# MysensorsATSHA_EEprom.net
KiCad netlist of a schematic drawn in EAGLE
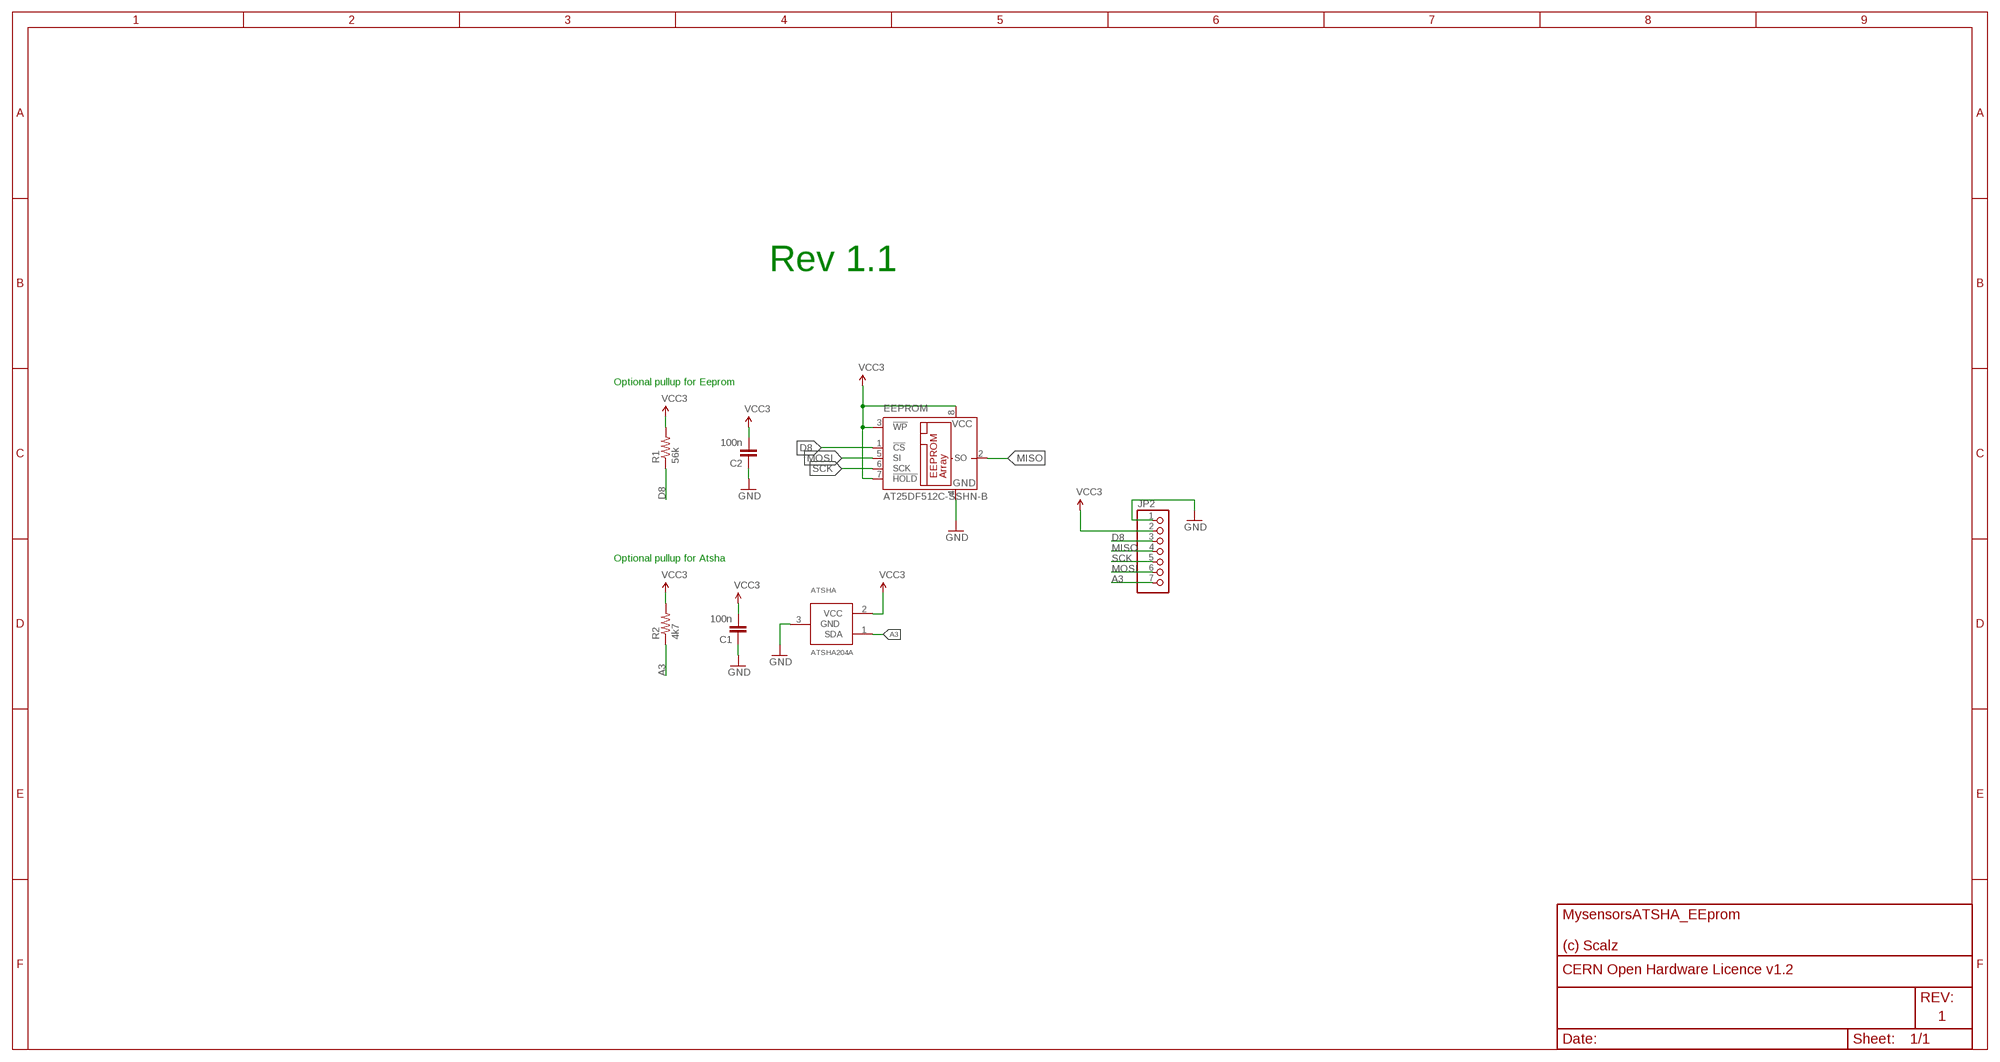
[diagram p0: schematic, sheet 1]

(export (version "E")
  (design (tool "Eeschema 10.0.6"))
  (components
    (comp (ref "ATSHA")
      (value "ATSHA204A")
      (footprint "eagle-import:SOT23")
      (libsource (lib "eagle-import") (part "ATSHA204A"))
    )
    (comp (ref "C1")
      (value "100n")
      (footprint "eagle-import:1206")
      (libsource (lib "eagle-import") (part "CAP1206"))
    )
    (comp (ref "C2")
      (value "100n")
      (footprint "eagle-import:1206")
      (libsource (lib "eagle-import") (part "CAP1206"))
    )
    (comp (ref "EEPROM")
      (value "AT25DF512C-SSHN-B")
      (footprint "eagle-import:SO-08")
      (fields (field (name "MF") "MICROCHIP") (field (name "MPN") "25AA080/SN"))
      (libsource (lib "eagle-import") (part "25SNAA080"))
    )
    (comp (ref "JP2")
      (value "PINHD-1X7")
      (footprint "eagle-import:1X07")
      (libsource (lib "eagle-import") (part "PINHD-1X7"))
    )
    (comp (ref "R1")
      (value "56k")
      (footprint "eagle-import:1206")
      (libsource (lib "eagle-import") (part "RESISTOR1206"))
    )
    (comp (ref "R2")
      (value "4k7")
      (footprint "eagle-import:1206")
      (libsource (lib "eagle-import") (part "RESISTOR1206"))
    )
  )
  (nets
    (net (code "1") (name "A3") (class "Default")
      (node (ref "ATSHA") (pin "1") (pinfunction "SDA_1") (pintype "bidirectional"))
      (node (ref "JP2") (pin "7") (pinfunction "7_7") (pintype "passive"))
      (node (ref "R2") (pin "1") (pinfunction "1_1") (pintype "passive"))
    )
    (net (code "2") (name "D8") (class "Default")
      (node (ref "EEPROM") (pin "1") (pinfunction "~{CS}_1") (pintype "input"))
      (node (ref "JP2") (pin "3") (pinfunction "3_3") (pintype "passive"))
      (node (ref "R1") (pin "1") (pinfunction "1_1") (pintype "passive"))
    )
    (net (code "3") (name "GND") (class "Default")
      (node (ref "ATSHA") (pin "3") (pinfunction "GND_3") (pintype "bidirectional"))
      (node (ref "C1") (pin "1") (pinfunction "1_1") (pintype "passive"))
      (node (ref "C2") (pin "1") (pinfunction "1_1") (pintype "passive"))
      (node (ref "EEPROM") (pin "4") (pinfunction "GND_4") (pintype "power_in"))
      (node (ref "JP2") (pin "1") (pinfunction "1_1") (pintype "passive"))
    )
    (net (code "4") (name "MISO") (class "Default")
      (node (ref "EEPROM") (pin "2") (pinfunction "SO_2") (pintype "bidirectional"))
      (node (ref "JP2") (pin "4") (pinfunction "4_4") (pintype "passive"))
    )
    (net (code "5") (name "MOSI") (class "Default")
      (node (ref "EEPROM") (pin "5") (pinfunction "SI_5") (pintype "input"))
      (node (ref "JP2") (pin "6") (pinfunction "6_6") (pintype "passive"))
    )
    (net (code "6") (name "SCK") (class "Default")
      (node (ref "EEPROM") (pin "6") (pinfunction "SCK_6") (pintype "input"))
      (node (ref "JP2") (pin "5") (pinfunction "5_5") (pintype "passive"))
    )
    (net (code "7") (name "VCC3") (class "Default")
      (node (ref "ATSHA") (pin "2") (pinfunction "VCC_2") (pintype "bidirectional"))
      (node (ref "C1") (pin "2") (pinfunction "2_2") (pintype "passive"))
      (node (ref "C2") (pin "2") (pinfunction "2_2") (pintype "passive"))
      (node (ref "EEPROM") (pin "3") (pinfunction "~{WP}_3") (pintype "input"))
      (node (ref "EEPROM") (pin "7") (pinfunction "~{HOLD}_7") (pintype "input"))
      (node (ref "EEPROM") (pin "8") (pinfunction "VCC_8") (pintype "power_in"))
      (node (ref "JP2") (pin "2") (pinfunction "2_2") (pintype "passive"))
      (node (ref "R1") (pin "2") (pinfunction "2_2") (pintype "passive"))
      (node (ref "R2") (pin "2") (pinfunction "2_2") (pintype "passive"))
    )
  )
)
